# max1626.net
KiCad netlist of a schematic drawn in EAGLE
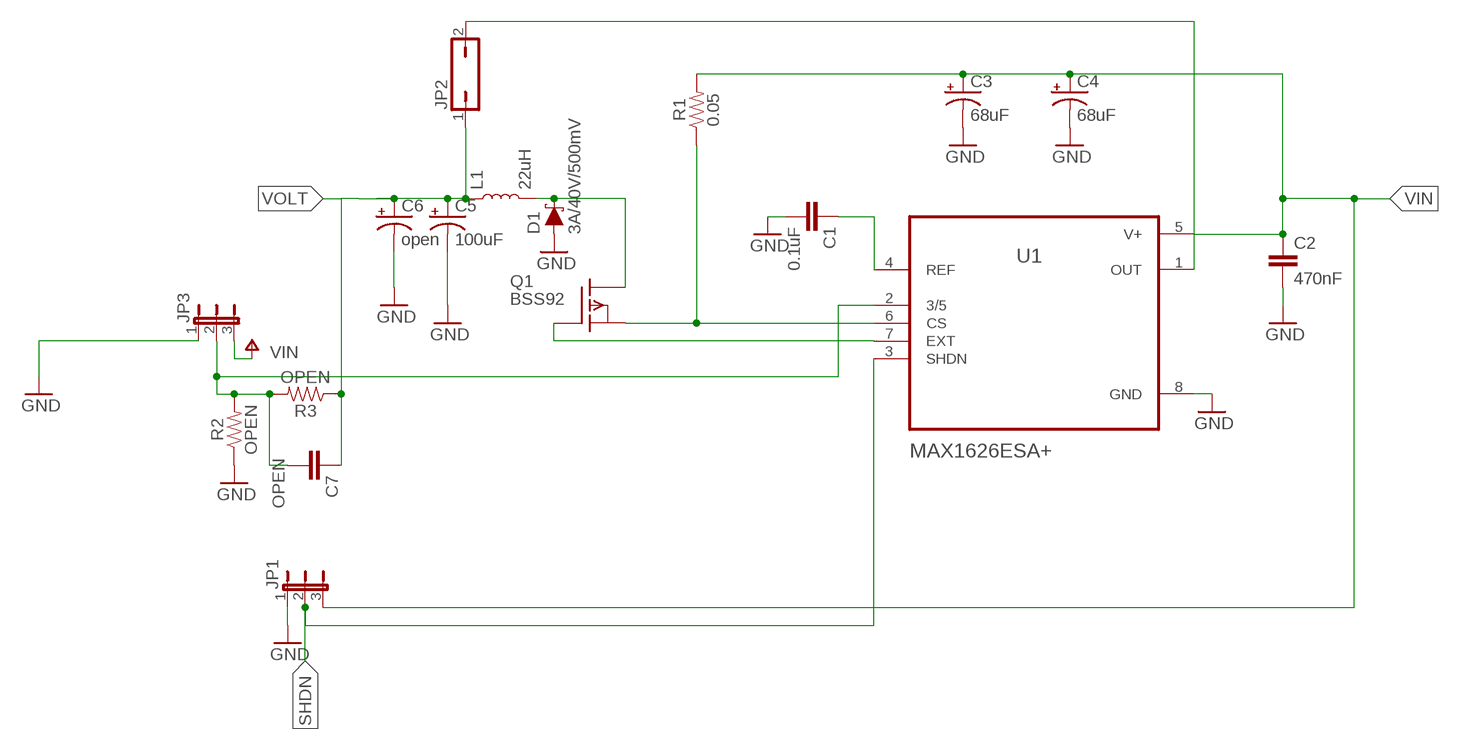
[diagram p0: schematic, sheet 1]

(export (version "E")
  (design (tool "Eeschema 10.0.6"))
  (components
    (comp (ref "C1")
      (value "0.1uF")
      (footprint "eagle-import:0603")
      (libsource (lib "eagle-import") (part "0.1UF-0603-25V-(+80/-20%)"))
    )
    (comp (ref "C2")
      (value "470nF")
      (footprint "eagle-import:0603")
      (libsource (lib "eagle-import") (part "470NF-0603-10V-10%-X5R"))
    )
    (comp (ref "C3")
      (value "68uF")
      (footprint "eagle-import:EIA3528")
      (libsource (lib "eagle-import") (part "68UF-POLAR-EIA3528-10V-10%(TANT)"))
    )
    (comp (ref "C4")
      (value "68uF")
      (footprint "eagle-import:EIA3528")
      (libsource (lib "eagle-import") (part "68UF-POLAR-EIA3528-10V-10%(TANT)"))
    )
    (comp (ref "C5")
      (value "100uF")
      (footprint "eagle-import:NIC_10X10.5_CAP")
      (libsource (lib "eagle-import") (part "100UF-POLAR-10X10.5-63V-20%"))
    )
    (comp (ref "C6")
      (value "open")
      (footprint "eagle-import:NIC_10X10.5_CAP")
      (libsource (lib "eagle-import") (part "100UF-POLAR-10X10.5-63V-20%"))
    )
    (comp (ref "C7")
      (value "OPEN")
      (footprint "eagle-import:0603")
      (libsource (lib "eagle-import") (part "0.1UF-0603-25V-(+80/-20%)"))
    )
    (comp (ref "D1")
      (value "3A/40V/500mV")
      (footprint "eagle-import:SMA-DIODE")
      (libsource (lib "eagle-import") (part "DIODE-SCHOTTKY-B340A"))
    )
    (comp (ref "JP1")
      (value "JP2W")
      (footprint "eagle-import:JP2W")
      (libsource (lib "eagle-import") (part "JP2W"))
    )
    (comp (ref "JP2")
      (value "JP1Q")
      (footprint "eagle-import:JP1")
      (libsource (lib "eagle-import") (part "JP1Q"))
    )
    (comp (ref "JP3")
      (value "JP2W")
      (footprint "eagle-import:JP2W")
      (libsource (lib "eagle-import") (part "JP2W"))
    )
    (comp (ref "L1")
      (value "22uH")
      (footprint "eagle-import:XFL4020")
      (libsource (lib "eagle-import") (part "INDUCTOR"))
    )
    (comp (ref "Q1")
      (value "BSS92")
      (footprint "eagle-import:TO92")
      (libsource (lib "eagle-import") (part "BSS92"))
    )
    (comp (ref "R1")
      (value "0.05")
      (footprint "eagle-import:0603")
      (libsource (lib "eagle-import") (part "0.05OHM-0603-1/5W-1%"))
    )
    (comp (ref "R2")
      (value "OPEN")
      (footprint "eagle-import:0603")
      (libsource (lib "eagle-import") (part "0.05OHM-0603-1/5W-1%"))
    )
    (comp (ref "R3")
      (value "OPEN")
      (footprint "eagle-import:0603")
      (libsource (lib "eagle-import") (part "0.05OHM-0603-1/5W-1%"))
    )
    (comp (ref "U1")
      (value "MAX1626ESA+")
      (footprint "eagle-import:SOIC127P600X175-8N")
      (fields (field (name "MF") "Maxim Integrated"))
      (libsource (lib "eagle-import") (part "MAX1626ESA+"))
    )
  )
  (nets
    (net (code "1") (name "GND") (class "Default")
      (node (ref "C1") (pin "2") (pinfunction "2_2") (pintype "passive"))
      (node (ref "C2") (pin "2") (pinfunction "2_2") (pintype "passive"))
      (node (ref "C3") (pin "C") (pinfunction "-_C") (pintype "passive"))
      (node (ref "C4") (pin "C") (pinfunction "-_C") (pintype "passive"))
      (node (ref "C5") (pin "-") (pinfunction "-_-") (pintype "passive"))
      (node (ref "C6") (pin "-") (pinfunction "-_-") (pintype "passive"))
      (node (ref "D1") (pin "A") (pinfunction "A_A") (pintype "passive"))
      (node (ref "JP1") (pin "1") (pinfunction "1_1") (pintype "passive"))
      (node (ref "JP3") (pin "1") (pinfunction "1_1") (pintype "passive"))
      (node (ref "R2") (pin "1") (pinfunction "1_1") (pintype "passive"))
      (node (ref "U1") (pin "8") (pinfunction "GND_8") (pintype "power_in"))
    )
    (net (code "2") (name "Net-(L1-2)") (class "Default")
      (node (ref "D1") (pin "C") (pinfunction "C_C") (pintype "passive"))
      (node (ref "L1") (pin "P$2") (pinfunction "2_P$2") (pintype "passive"))
      (node (ref "Q1") (pin "2") (pinfunction "D_2") (pintype "passive"))
    )
    (net (code "3") (name "Net-(Q1-G)") (class "Default")
      (node (ref "Q1") (pin "1") (pinfunction "G_1") (pintype "passive"))
      (node (ref "U1") (pin "7") (pinfunction "EXT_7") (pintype "bidirectional"))
    )
    (net (code "4") (name "Net-(Q1-S)") (class "Default")
      (node (ref "Q1") (pin "3") (pinfunction "S_3") (pintype "passive"))
      (node (ref "R1") (pin "1") (pinfunction "1_1") (pintype "passive"))
      (node (ref "U1") (pin "6") (pinfunction "CS_6") (pintype "bidirectional"))
    )
    (net (code "5") (name "Net-(U1-3{slash}5)") (class "Default")
      (node (ref "C7") (pin "2") (pinfunction "2_2") (pintype "passive"))
      (node (ref "JP3") (pin "2") (pinfunction "2_2") (pintype "passive"))
      (node (ref "R2") (pin "2") (pinfunction "2_2") (pintype "passive"))
      (node (ref "R3") (pin "2") (pinfunction "2_2") (pintype "passive"))
      (node (ref "U1") (pin "2") (pinfunction "3/5_2") (pintype "bidirectional"))
    )
    (net (code "6") (name "Net-(U1-OUT)") (class "Default")
      (node (ref "JP2") (pin "2") (pinfunction "2_2") (pintype "passive"))
      (node (ref "U1") (pin "1") (pinfunction "OUT_1") (pintype "output"))
    )
    (net (code "7") (name "Net-(U1-REF)") (class "Default")
      (node (ref "C1") (pin "1") (pinfunction "1_1") (pintype "passive"))
      (node (ref "U1") (pin "4") (pinfunction "REF_4") (pintype "input"))
    )
    (net (code "8") (name "SHDN") (class "Default")
      (node (ref "JP1") (pin "2") (pinfunction "2_2") (pintype "passive"))
      (node (ref "U1") (pin "3") (pinfunction "SHDN_3") (pintype "bidirectional"))
    )
    (net (code "9") (name "VIN") (class "Default")
      (node (ref "C2") (pin "1") (pinfunction "1_1") (pintype "passive"))
      (node (ref "C3") (pin "A") (pinfunction "+_A") (pintype "passive"))
      (node (ref "C4") (pin "A") (pinfunction "+_A") (pintype "passive"))
      (node (ref "JP1") (pin "3") (pinfunction "3_3") (pintype "passive"))
      (node (ref "JP3") (pin "3") (pinfunction "3_3") (pintype "passive"))
      (node (ref "R1") (pin "2") (pinfunction "2_2") (pintype "passive"))
      (node (ref "U1") (pin "5") (pinfunction "V+_5") (pintype "power_in"))
    )
    (net (code "10") (name "VOLT") (class "Default")
      (node (ref "C5") (pin "+") (pinfunction "+_+") (pintype "passive"))
      (node (ref "C6") (pin "+") (pinfunction "+_+") (pintype "passive"))
      (node (ref "C7") (pin "1") (pinfunction "1_1") (pintype "passive"))
      (node (ref "JP2") (pin "1") (pinfunction "1_1") (pintype "passive"))
      (node (ref "L1") (pin "P$1") (pinfunction "1_P$1") (pintype "passive"))
      (node (ref "R3") (pin "1") (pinfunction "1_1") (pintype "passive"))
    )
  )
)
